# Buttonz.net
KiCad netlist of a schematic drawn in Altium Designer
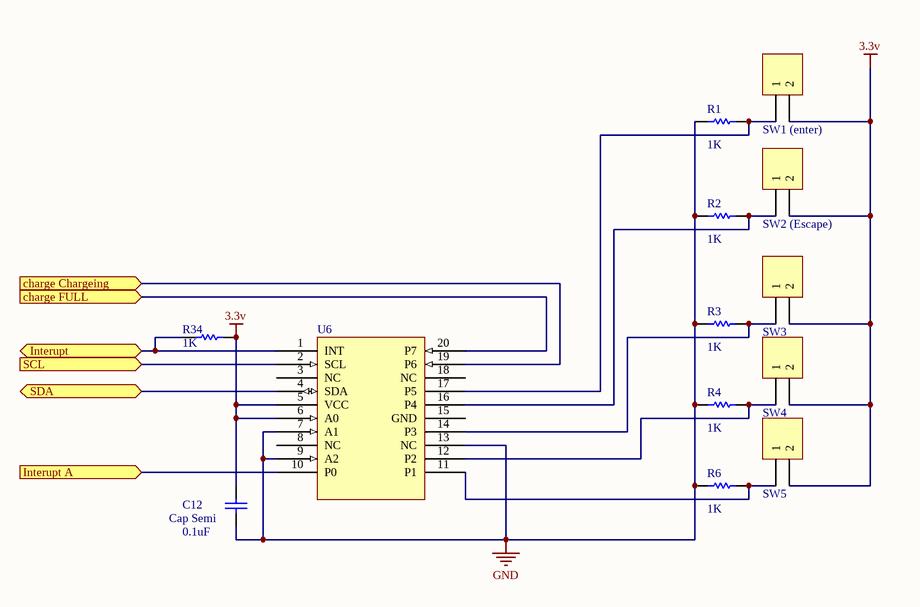
[diagram p0: Buttonz.SchDoc]

(export (version "E")
  (design (tool "Eeschema 10.0.6"))
  (components
    (comp (ref "C12")
      (value "Cap Semi")
      (footprint "C1206")
      (description "Capacitor (Semiconductor SIM Model)")
      (fields (field (name "ALTIUM_VALUE") "0.1uF") (field (name "PUBLISHER") "Altium Limited"))
      (libsource (lib "Miscellaneous Devices") (part "Cap Semi"))
    )
    (comp (ref "P40")
      (value "SW1 (enter)")
      (footprint "HDR1X2")
      (description "Header, 2-Pin")
      (fields (field (name "PUBLISHER") "Altium Limited"))
      (libsource (lib "Miscellaneous Connectors") (part "Header 2"))
    )
    (comp (ref "P41")
      (value "SW2 (Escape)")
      (footprint "HDR1X2")
      (description "Header, 2-Pin")
      (fields (field (name "PUBLISHER") "Altium Limited"))
      (libsource (lib "Miscellaneous Connectors") (part "Header 2"))
    )
    (comp (ref "P42")
      (value "SW3")
      (footprint "HDR1X2")
      (description "Header, 2-Pin")
      (fields (field (name "PUBLISHER") "Altium Limited"))
      (libsource (lib "Miscellaneous Connectors") (part "Header 2"))
    )
    (comp (ref "P43")
      (value "SW4")
      (footprint "HDR1X2")
      (description "Header, 2-Pin")
      (fields (field (name "PUBLISHER") "Altium Limited"))
      (libsource (lib "Miscellaneous Connectors") (part "Header 2"))
    )
    (comp (ref "P44")
      (value "SW5")
      (footprint "HDR1X2")
      (description "Header, 2-Pin")
      (fields (field (name "PUBLISHER") "Altium Limited"))
      (libsource (lib "Miscellaneous Connectors") (part "Header 2"))
    )
    (comp (ref "R1")
      (value "1K")
      (footprint "0402")
      (description "Resistor")
      (fields (field (name "Comment") "Res1") (field (name "PUBLISHER") "Altium Limited"))
      (libsource (lib "Miscellaneous Devices") (part "Res1"))
    )
    (comp (ref "R2")
      (value "1K")
      (footprint "0402")
      (description "Resistor")
      (fields (field (name "Comment") "Res1") (field (name "PUBLISHER") "Altium Limited"))
      (libsource (lib "Miscellaneous Devices") (part "Res1"))
    )
    (comp (ref "R3")
      (value "1K")
      (footprint "0402")
      (description "Resistor")
      (fields (field (name "Comment") "Res1") (field (name "PUBLISHER") "Altium Limited"))
      (libsource (lib "Miscellaneous Devices") (part "Res1"))
    )
    (comp (ref "R4")
      (value "1K")
      (footprint "0402")
      (description "Resistor")
      (fields (field (name "Comment") "Res1") (field (name "PUBLISHER") "Altium Limited"))
      (libsource (lib "Miscellaneous Devices") (part "Res1"))
    )
    (comp (ref "R6")
      (value "1K")
      (footprint "0402")
      (description "Resistor")
      (fields (field (name "Comment") "Res1") (field (name "PUBLISHER") "Altium Limited"))
      (libsource (lib "Miscellaneous Devices") (part "Res1"))
    )
    (comp (ref "R34")
      (value "1K")
      (footprint "0402")
      (description "Resistor")
      (fields (field (name "Comment") "Res1") (field (name "PUBLISHER") "Altium Limited"))
      (libsource (lib "Miscellaneous Devices") (part "Res1"))
    )
    (comp (ref "U6")
      (value "Component_1")
      (footprint "SOP20")
      (libsource (lib "PCF8574") (part "Component_1"))
    )
  )
  (nets
    (net (code "1") (name "/Interupt") (class "Default")
      (node (ref "R34") (pin "1") (pinfunction "1_1") (pintype "passive"))
      (node (ref "U6") (pin "1") (pinfunction "INT_1") (pintype "passive"))
    )
    (net (code "2") (name "/Interupt A") (class "Default")
      (node (ref "U6") (pin "10") (pinfunction "P0_10") (pintype "passive"))
    )
    (net (code "3") (name "/SCL") (class "Default")
      (node (ref "U6") (pin "2") (pinfunction "SCL_2") (pintype "input"))
    )
    (net (code "4") (name "/SDA") (class "Default")
      (node (ref "U6") (pin "4") (pinfunction "SDA_4") (pintype "bidirectional"))
    )
    (net (code "5") (name "/charge Chargeing") (class "Default")
      (node (ref "U6") (pin "19") (pinfunction "P6_19") (pintype "input"))
    )
    (net (code "6") (name "/charge FULL") (class "Default")
      (node (ref "U6") (pin "20") (pinfunction "P7_20") (pintype "input"))
    )
    (net (code "7") (name "3.3v") (class "Default")
      (node (ref "C12") (pin "2") (pinfunction "2_2") (pintype "passive"))
      (node (ref "P40") (pin "2") (pinfunction "2_2") (pintype "passive"))
      (node (ref "P41") (pin "2") (pinfunction "2_2") (pintype "passive"))
      (node (ref "P42") (pin "2") (pinfunction "2_2") (pintype "passive"))
      (node (ref "P43") (pin "2") (pinfunction "2_2") (pintype "passive"))
      (node (ref "P44") (pin "2") (pinfunction "2_2") (pintype "passive"))
      (node (ref "R34") (pin "2") (pinfunction "2_2") (pintype "passive"))
      (node (ref "U6") (pin "5") (pinfunction "VCC_5") (pintype "power_in"))
      (node (ref "U6") (pin "6") (pinfunction "A0_6") (pintype "input"))
    )
    (net (code "8") (name "GND") (class "Default")
      (node (ref "C12") (pin "1") (pinfunction "1_1") (pintype "passive"))
      (node (ref "R1") (pin "1") (pinfunction "1_1") (pintype "passive"))
      (node (ref "R2") (pin "1") (pinfunction "1_1") (pintype "passive"))
      (node (ref "R3") (pin "1") (pinfunction "1_1") (pintype "passive"))
      (node (ref "R4") (pin "1") (pinfunction "1_1") (pintype "passive"))
      (node (ref "R6") (pin "1") (pinfunction "1_1") (pintype "passive"))
      (node (ref "U6") (pin "13") (pinfunction "NC_13") (pintype "passive"))
      (node (ref "U6") (pin "7") (pinfunction "A1_7") (pintype "input"))
      (node (ref "U6") (pin "9") (pinfunction "A2_9") (pintype "input"))
    )
    (net (code "9") (name "Net-(U6-P1)") (class "Default")
      (node (ref "P44") (pin "1") (pinfunction "1_1") (pintype "passive"))
      (node (ref "R6") (pin "2") (pinfunction "2_2") (pintype "passive"))
      (node (ref "U6") (pin "11") (pinfunction "P1_11") (pintype "passive"))
    )
    (net (code "10") (name "Net-(U6-P2)") (class "Default")
      (node (ref "P43") (pin "1") (pinfunction "1_1") (pintype "passive"))
      (node (ref "R4") (pin "2") (pinfunction "2_2") (pintype "passive"))
      (node (ref "U6") (pin "12") (pinfunction "P2_12") (pintype "passive"))
    )
    (net (code "11") (name "Net-(U6-P3)") (class "Default")
      (node (ref "P42") (pin "1") (pinfunction "1_1") (pintype "passive"))
      (node (ref "R3") (pin "2") (pinfunction "2_2") (pintype "passive"))
      (node (ref "U6") (pin "14") (pinfunction "P3_14") (pintype "passive"))
    )
    (net (code "12") (name "Net-(U6-P4)") (class "Default")
      (node (ref "P41") (pin "1") (pinfunction "1_1") (pintype "passive"))
      (node (ref "R2") (pin "2") (pinfunction "2_2") (pintype "passive"))
      (node (ref "U6") (pin "16") (pinfunction "P4_16") (pintype "passive"))
    )
    (net (code "13") (name "Net-(U6-P5)") (class "Default")
      (node (ref "P40") (pin "1") (pinfunction "1_1") (pintype "passive"))
      (node (ref "R1") (pin "2") (pinfunction "2_2") (pintype "passive"))
      (node (ref "U6") (pin "17") (pinfunction "P5_17") (pintype "passive"))
    )
    (net (code "14") (name "unconnected-(U6-GND-Pad15)") (class "Default")
      (node (ref "U6") (pin "15") (pinfunction "GND_15") (pintype "power_in"))
    )
    (net (code "15") (name "unconnected-(U6-NC-Pad3)") (class "Default")
      (node (ref "U6") (pin "3") (pinfunction "NC_3") (pintype "passive"))
    )
    (net (code "16") (name "unconnected-(U6-NC-Pad8)") (class "Default")
      (node (ref "U6") (pin "8") (pinfunction "NC_8") (pintype "passive"))
    )
    (net (code "17") (name "unconnected-(U6-NC-Pad18)") (class "Default")
      (node (ref "U6") (pin "18") (pinfunction "NC_18") (pintype "passive"))
    )
  )
)
